# Schematic_without_SD_Card.net
KiCad netlist of a schematic drawn in EAGLE
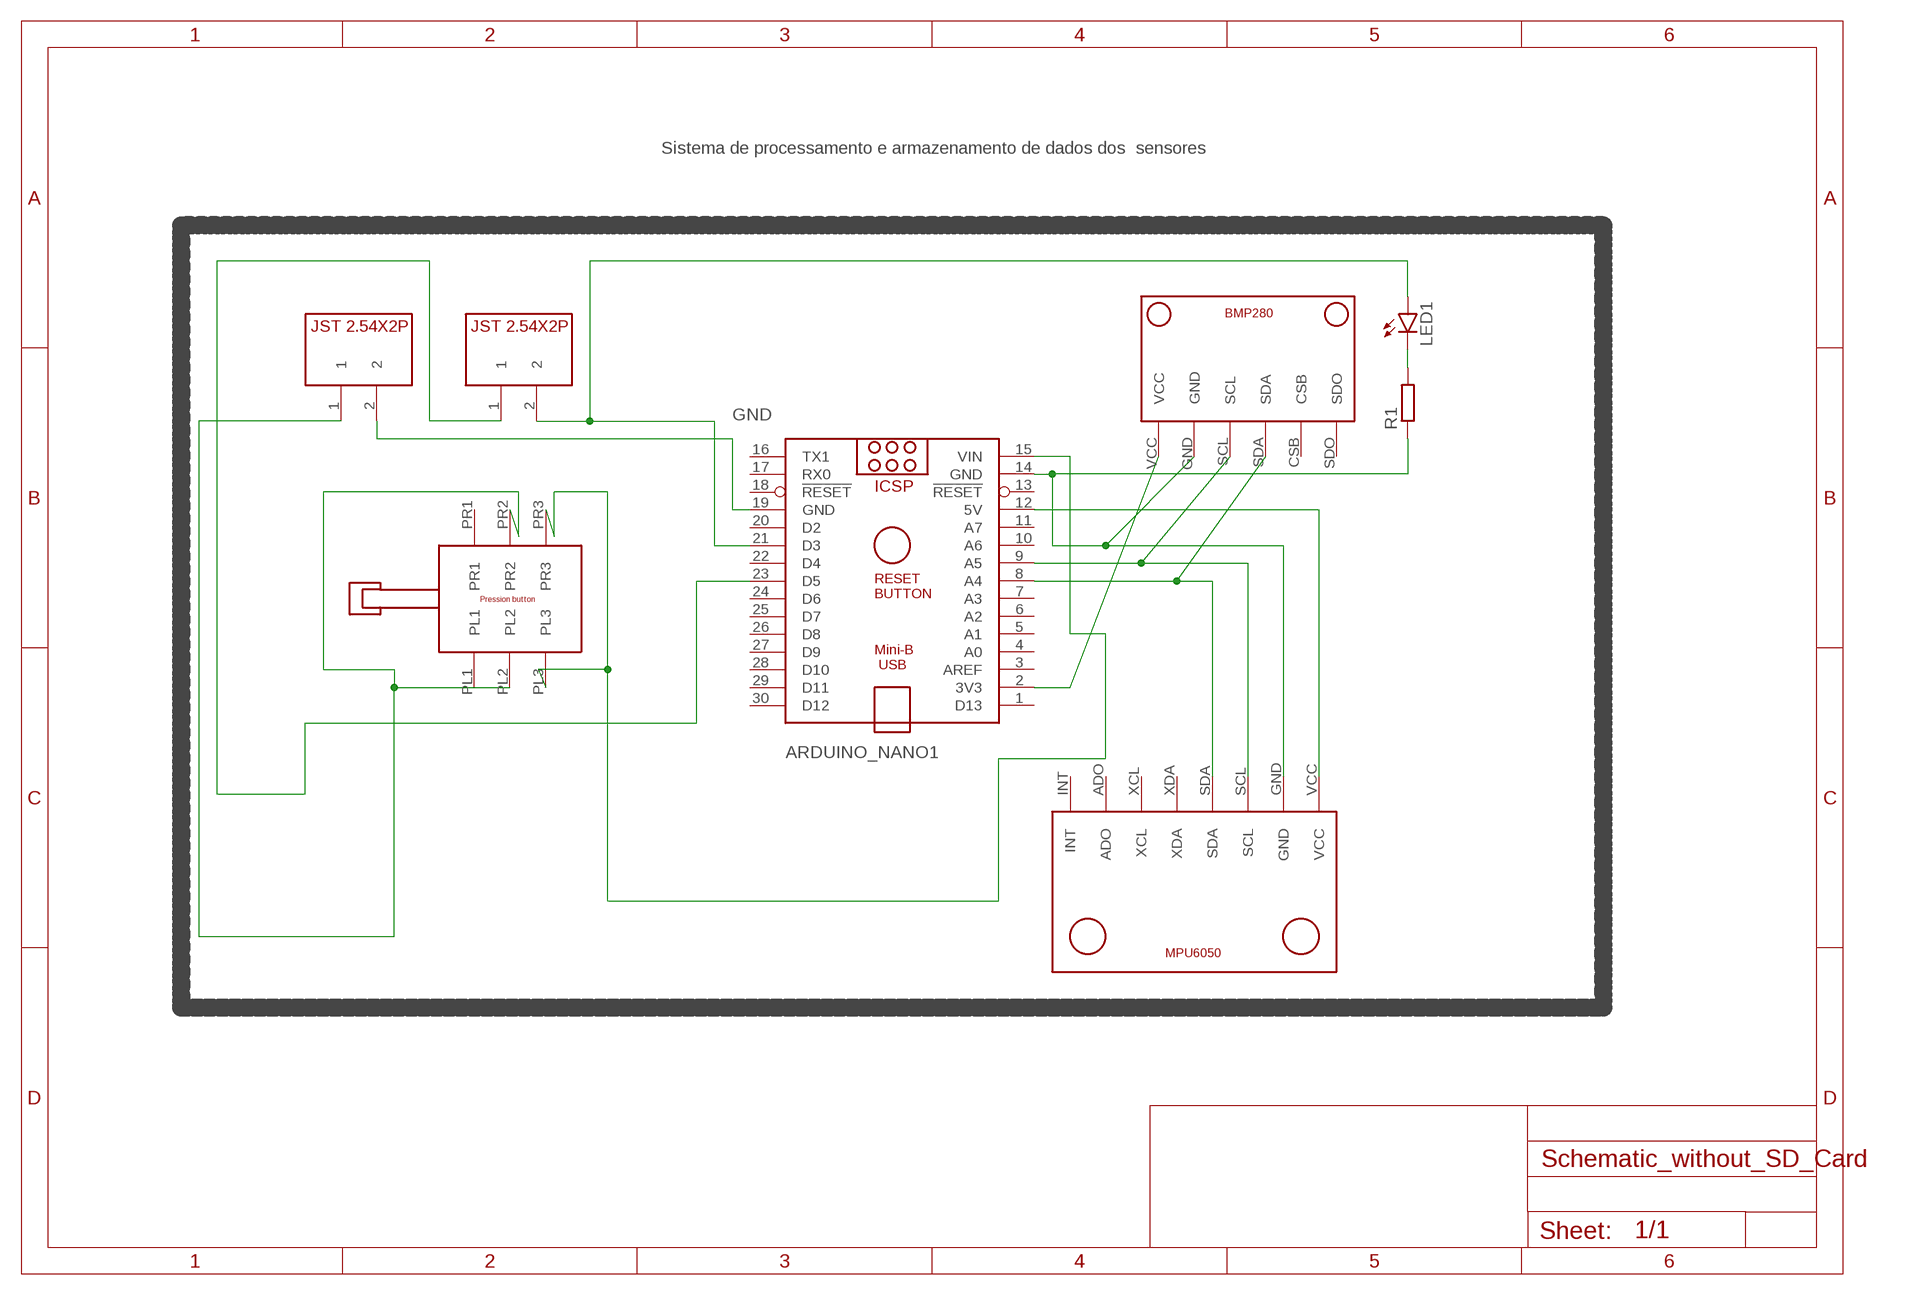
[diagram p0: schematic, sheet 1]

(export (version "E")
  (design (tool "Eeschema 10.0.6"))
  (components
    (comp (ref "ARDUINO_NANO1")
      (value "ARDUINO_NANO")
      (footprint "eagle-import:ARDUINO_NANO")
      (libsource (lib "eagle-import") (part "ARDUINO_NANO"))
    )
    (comp (ref "LED1")
      (value "LED5MM")
      (footprint "eagle-import:LED5MM")
      (libsource (lib "eagle-import") (part "LED5MM"))
    )
    (comp (ref "R1")
      (value "R-EU_0207/10")
      (footprint "eagle-import:0207_10")
      (libsource (lib "eagle-import") (part "R-EU_0207/10"))
    )
    (comp (ref "U$1")
      (value "BMP280V1")
      (footprint "eagle-import:BMP280_FOOTPRINT")
      (libsource (lib "eagle-import") (part "BMP280V1"))
    )
    (comp (ref "U$2")
      (value "MPU6050V1")
      (footprint "eagle-import:MPU6050_FOOTPRINT")
      (libsource (lib "eagle-import") (part "MPU6050V1"))
    )
    (comp (ref "U$3")
      (value "PRESSION_BUTTON")
      (footprint "eagle-import:PRESSION_BUTTON_FOOTPRINT")
      (libsource (lib "eagle-import") (part "PRESSION_BUTTON"))
    )
    (comp (ref "U$5")
      (value "JST2.54X2P")
      (footprint "eagle-import:JST2.54X2P_FOOTPRINT")
      (libsource (lib "eagle-import") (part "JST2.54X2P"))
    )
    (comp (ref "U$6")
      (value "JST2.54X2P")
      (footprint "eagle-import:JST2.54X2P_FOOTPRINT")
      (libsource (lib "eagle-import") (part "JST2.54X2P"))
    )
  )
  (nets
    (net (code "1") (name "/GND") (class "Default")
      (node (ref "ARDUINO_NANO1") (pin "14") (pinfunction "GND_14") (pintype "power_in"))
      (node (ref "ARDUINO_NANO1") (pin "19") (pinfunction "GND_19") (pintype "power_in"))
      (node (ref "R1") (pin "1") (pinfunction "1_1") (pintype "passive"))
      (node (ref "U$1") (pin "GND") (pinfunction "GND_GND") (pintype "bidirectional"))
      (node (ref "U$2") (pin "GND") (pinfunction "GND_GND") (pintype "bidirectional"))
      (node (ref "U$6") (pin "2") (pinfunction "2_2") (pintype "bidirectional"))
    )
    (net (code "2") (name "Net-(ARDUINO_NANO1-3V3)") (class "Default")
      (node (ref "ARDUINO_NANO1") (pin "2") (pinfunction "3V3_2") (pintype "output"))
      (node (ref "U$1") (pin "VCC") (pinfunction "VCC_VCC") (pintype "bidirectional"))
    )
    (net (code "3") (name "Net-(ARDUINO_NANO1-5V)") (class "Default")
      (node (ref "ARDUINO_NANO1") (pin "12") (pinfunction "5V_12") (pintype "power_in"))
      (node (ref "U$2") (pin "VCC") (pinfunction "VCC_VCC") (pintype "bidirectional"))
    )
    (net (code "4") (name "Net-(ARDUINO_NANO1-A4)") (class "Default")
      (node (ref "ARDUINO_NANO1") (pin "8") (pinfunction "A4_8") (pintype "bidirectional"))
      (node (ref "U$1") (pin "SDA") (pinfunction "SDA_SDA") (pintype "bidirectional"))
      (node (ref "U$2") (pin "SDA") (pinfunction "SDA_SDA") (pintype "bidirectional"))
    )
    (net (code "5") (name "Net-(ARDUINO_NANO1-A5)") (class "Default")
      (node (ref "ARDUINO_NANO1") (pin "9") (pinfunction "A5_9") (pintype "bidirectional"))
      (node (ref "U$1") (pin "SCL") (pinfunction "SCL_SCL") (pintype "bidirectional"))
      (node (ref "U$2") (pin "SCL") (pinfunction "SCL_SCL") (pintype "bidirectional"))
    )
    (net (code "6") (name "Net-(ARDUINO_NANO1-D3)") (class "Default")
      (node (ref "ARDUINO_NANO1") (pin "21") (pinfunction "D3_21") (pintype "bidirectional"))
      (node (ref "LED1") (pin "A") (pinfunction "A_A") (pintype "passive"))
      (node (ref "U$5") (pin "2") (pinfunction "2_2") (pintype "bidirectional"))
    )
    (net (code "7") (name "Net-(ARDUINO_NANO1-D5)") (class "Default")
      (node (ref "ARDUINO_NANO1") (pin "23") (pinfunction "D5_23") (pintype "bidirectional"))
      (node (ref "U$5") (pin "1") (pinfunction "1_1") (pintype "bidirectional"))
    )
    (net (code "8") (name "Net-(ARDUINO_NANO1-VIN)") (class "Default")
      (node (ref "ARDUINO_NANO1") (pin "15") (pinfunction "VIN_15") (pintype "power_in"))
      (node (ref "U$3") (pin "PL3") (pinfunction "PL3_PL3") (pintype "bidirectional"))
      (node (ref "U$3") (pin "PR3") (pinfunction "PR3_PR3") (pintype "bidirectional"))
    )
    (net (code "9") (name "Net-(LED1-C)") (class "Default")
      (node (ref "LED1") (pin "K") (pinfunction "C_K") (pintype "passive"))
      (node (ref "R1") (pin "2") (pinfunction "2_2") (pintype "passive"))
    )
    (net (code "10") (name "Net-(U$3-PadPL2)") (class "Default")
      (node (ref "U$3") (pin "PL2") (pinfunction "PL2_PL2") (pintype "bidirectional"))
      (node (ref "U$3") (pin "PR2") (pinfunction "PR2_PR2") (pintype "bidirectional"))
      (node (ref "U$6") (pin "1") (pinfunction "1_1") (pintype "bidirectional"))
    )
    (net (code "11") (name "unconnected-(ARDUINO_NANO1-A0-Pad4)") (class "Default")
      (node (ref "ARDUINO_NANO1") (pin "4") (pinfunction "A0_4") (pintype "bidirectional"))
    )
    (net (code "12") (name "unconnected-(ARDUINO_NANO1-A1-Pad5)") (class "Default")
      (node (ref "ARDUINO_NANO1") (pin "5") (pinfunction "A1_5") (pintype "bidirectional"))
    )
    (net (code "13") (name "unconnected-(ARDUINO_NANO1-A2-Pad6)") (class "Default")
      (node (ref "ARDUINO_NANO1") (pin "6") (pinfunction "A2_6") (pintype "bidirectional"))
    )
    (net (code "14") (name "unconnected-(ARDUINO_NANO1-A3-Pad7)") (class "Default")
      (node (ref "ARDUINO_NANO1") (pin "7") (pinfunction "A3_7") (pintype "bidirectional"))
    )
    (net (code "15") (name "unconnected-(ARDUINO_NANO1-A6-Pad10)") (class "Default")
      (node (ref "ARDUINO_NANO1") (pin "10") (pinfunction "A6_10") (pintype "bidirectional"))
    )
    (net (code "16") (name "unconnected-(ARDUINO_NANO1-A7-Pad11)") (class "Default")
      (node (ref "ARDUINO_NANO1") (pin "11") (pinfunction "A7_11") (pintype "bidirectional"))
    )
    (net (code "17") (name "unconnected-(ARDUINO_NANO1-AREF-Pad3)") (class "Default")
      (node (ref "ARDUINO_NANO1") (pin "3") (pinfunction "AREF_3") (pintype "input"))
    )
    (net (code "18") (name "unconnected-(ARDUINO_NANO1-D2-Pad20)") (class "Default")
      (node (ref "ARDUINO_NANO1") (pin "20") (pinfunction "D2_20") (pintype "bidirectional"))
    )
    (net (code "19") (name "unconnected-(ARDUINO_NANO1-D4-Pad22)") (class "Default")
      (node (ref "ARDUINO_NANO1") (pin "22") (pinfunction "D4_22") (pintype "bidirectional"))
    )
    (net (code "20") (name "unconnected-(ARDUINO_NANO1-D6-Pad24)") (class "Default")
      (node (ref "ARDUINO_NANO1") (pin "24") (pinfunction "D6_24") (pintype "bidirectional"))
    )
    (net (code "21") (name "unconnected-(ARDUINO_NANO1-D7-Pad25)") (class "Default")
      (node (ref "ARDUINO_NANO1") (pin "25") (pinfunction "D7_25") (pintype "bidirectional"))
    )
    (net (code "22") (name "unconnected-(ARDUINO_NANO1-D8-Pad26)") (class "Default")
      (node (ref "ARDUINO_NANO1") (pin "26") (pinfunction "D8_26") (pintype "bidirectional"))
    )
    (net (code "23") (name "unconnected-(ARDUINO_NANO1-D9-Pad27)") (class "Default")
      (node (ref "ARDUINO_NANO1") (pin "27") (pinfunction "D9_27") (pintype "bidirectional"))
    )
    (net (code "24") (name "unconnected-(ARDUINO_NANO1-D10-Pad28)") (class "Default")
      (node (ref "ARDUINO_NANO1") (pin "28") (pinfunction "D10_28") (pintype "bidirectional"))
    )
    (net (code "25") (name "unconnected-(ARDUINO_NANO1-D11-Pad29)") (class "Default")
      (node (ref "ARDUINO_NANO1") (pin "29") (pinfunction "D11_29") (pintype "bidirectional"))
    )
    (net (code "26") (name "unconnected-(ARDUINO_NANO1-D12-Pad30)") (class "Default")
      (node (ref "ARDUINO_NANO1") (pin "30") (pinfunction "D12_30") (pintype "bidirectional"))
    )
    (net (code "27") (name "unconnected-(ARDUINO_NANO1-D13-Pad1)") (class "Default")
      (node (ref "ARDUINO_NANO1") (pin "1") (pinfunction "D13_1") (pintype "bidirectional"))
    )
    (net (code "28") (name "unconnected-(ARDUINO_NANO1-RX0-Pad17)") (class "Default")
      (node (ref "ARDUINO_NANO1") (pin "17") (pinfunction "RX0_17") (pintype "bidirectional"))
    )
    (net (code "29") (name "unconnected-(ARDUINO_NANO1-TX1-Pad16)") (class "Default")
      (node (ref "ARDUINO_NANO1") (pin "16") (pinfunction "TX1_16") (pintype "bidirectional"))
    )
    (net (code "30") (name "unconnected-(ARDUINO_NANO1-~{RESET}-Pad13)") (class "Default")
      (node (ref "ARDUINO_NANO1") (pin "13") (pinfunction "~{RESET}_13") (pintype "input"))
    )
    (net (code "31") (name "unconnected-(ARDUINO_NANO1-~{RESET}-Pad18)") (class "Default")
      (node (ref "ARDUINO_NANO1") (pin "18") (pinfunction "~{RESET}_18") (pintype "input"))
    )
    (net (code "32") (name "unconnected-(U$1-PadCSB)") (class "Default")
      (node (ref "U$1") (pin "CSB") (pinfunction "CSB_CSB") (pintype "bidirectional"))
    )
    (net (code "33") (name "unconnected-(U$1-PadSDO)") (class "Default")
      (node (ref "U$1") (pin "SDO") (pinfunction "SDO_SDO") (pintype "bidirectional"))
    )
    (net (code "34") (name "unconnected-(U$2-PadADO)") (class "Default")
      (node (ref "U$2") (pin "ADO") (pinfunction "ADO_ADO") (pintype "bidirectional"))
    )
    (net (code "35") (name "unconnected-(U$2-PadINT)") (class "Default")
      (node (ref "U$2") (pin "INT") (pinfunction "INT_INT") (pintype "bidirectional"))
    )
    (net (code "36") (name "unconnected-(U$2-PadXCL)") (class "Default")
      (node (ref "U$2") (pin "XCL") (pinfunction "XCL_XCL") (pintype "bidirectional"))
    )
    (net (code "37") (name "unconnected-(U$2-PadXDA)") (class "Default")
      (node (ref "U$2") (pin "XDA") (pinfunction "XDA_XDA") (pintype "bidirectional"))
    )
    (net (code "38") (name "unconnected-(U$3-PadPL1)") (class "Default")
      (node (ref "U$3") (pin "PL1") (pinfunction "PL1_PL1") (pintype "bidirectional"))
    )
    (net (code "39") (name "unconnected-(U$3-PadPR1)") (class "Default")
      (node (ref "U$3") (pin "PR1") (pinfunction "PR1_PR1") (pintype "bidirectional"))
    )
  )
)
